# rev3.net
KiCad netlist of a schematic drawn in EAGLE
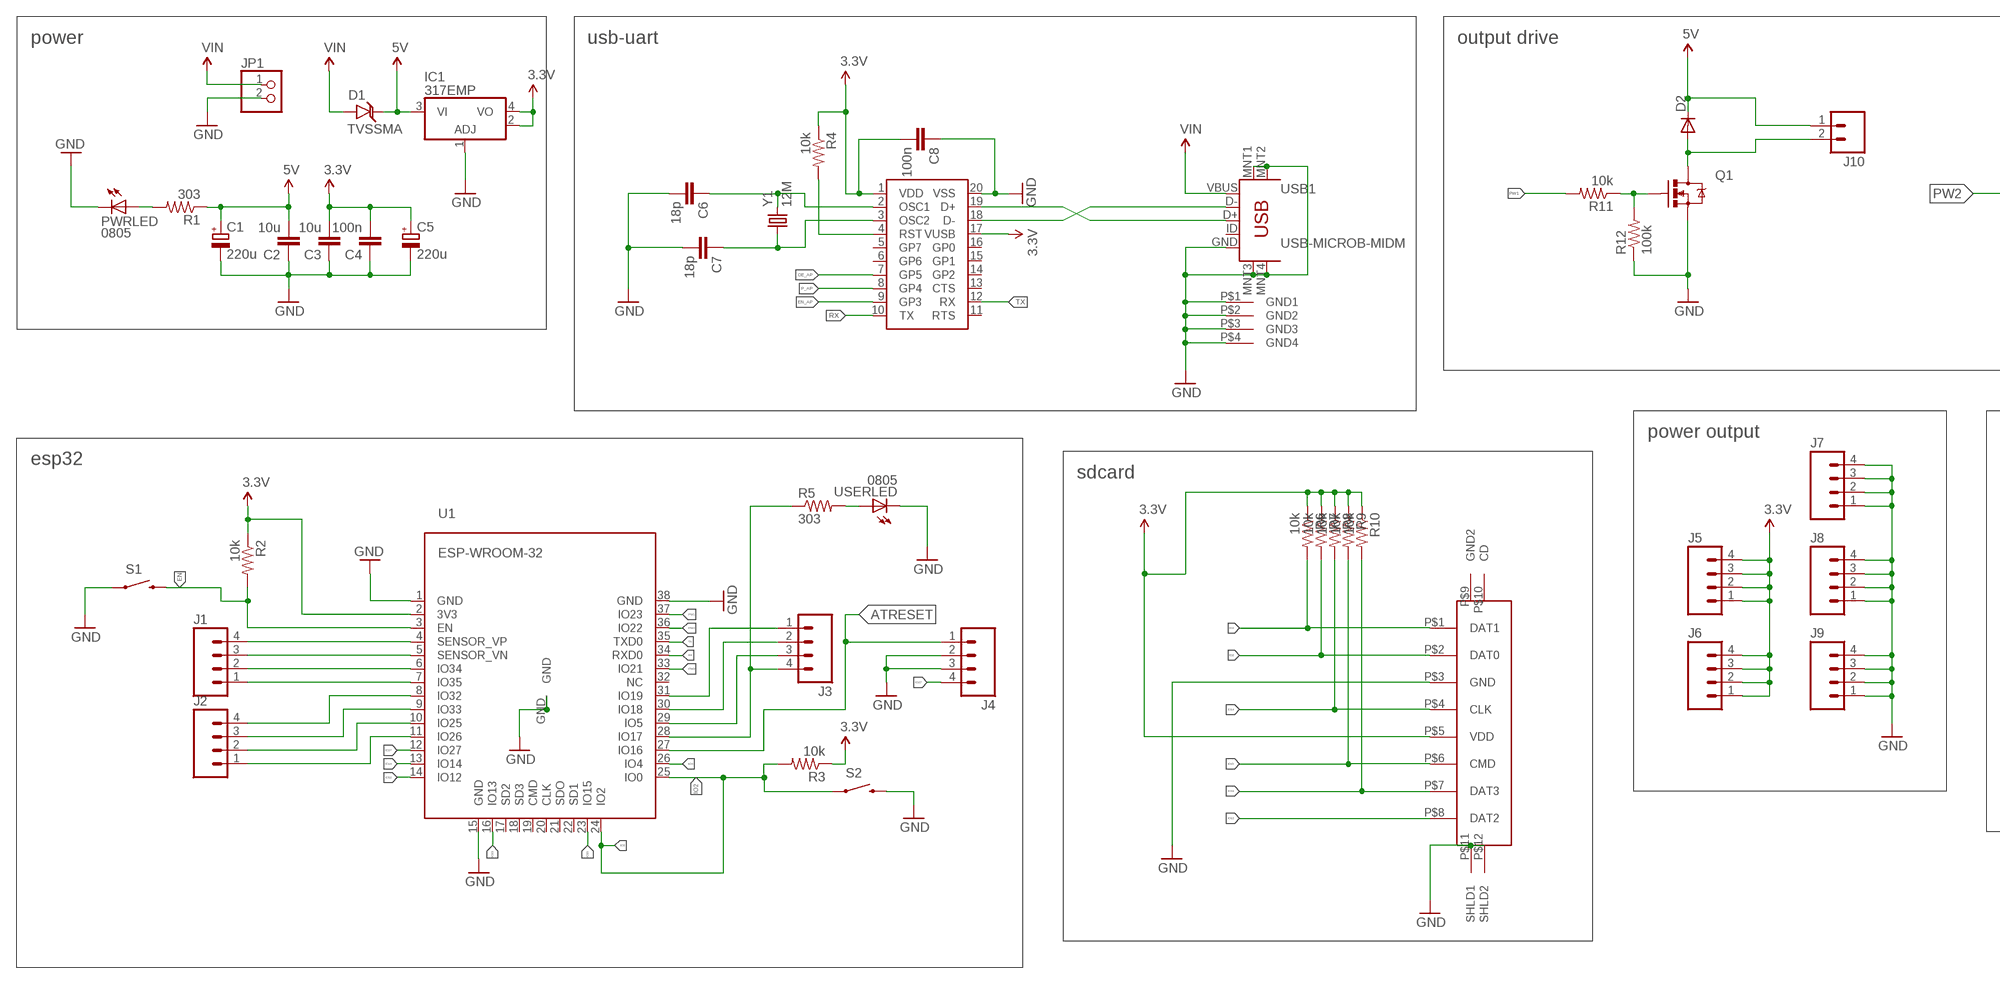
[diagram p0: schematic, sheet 1, part 1 of 2]
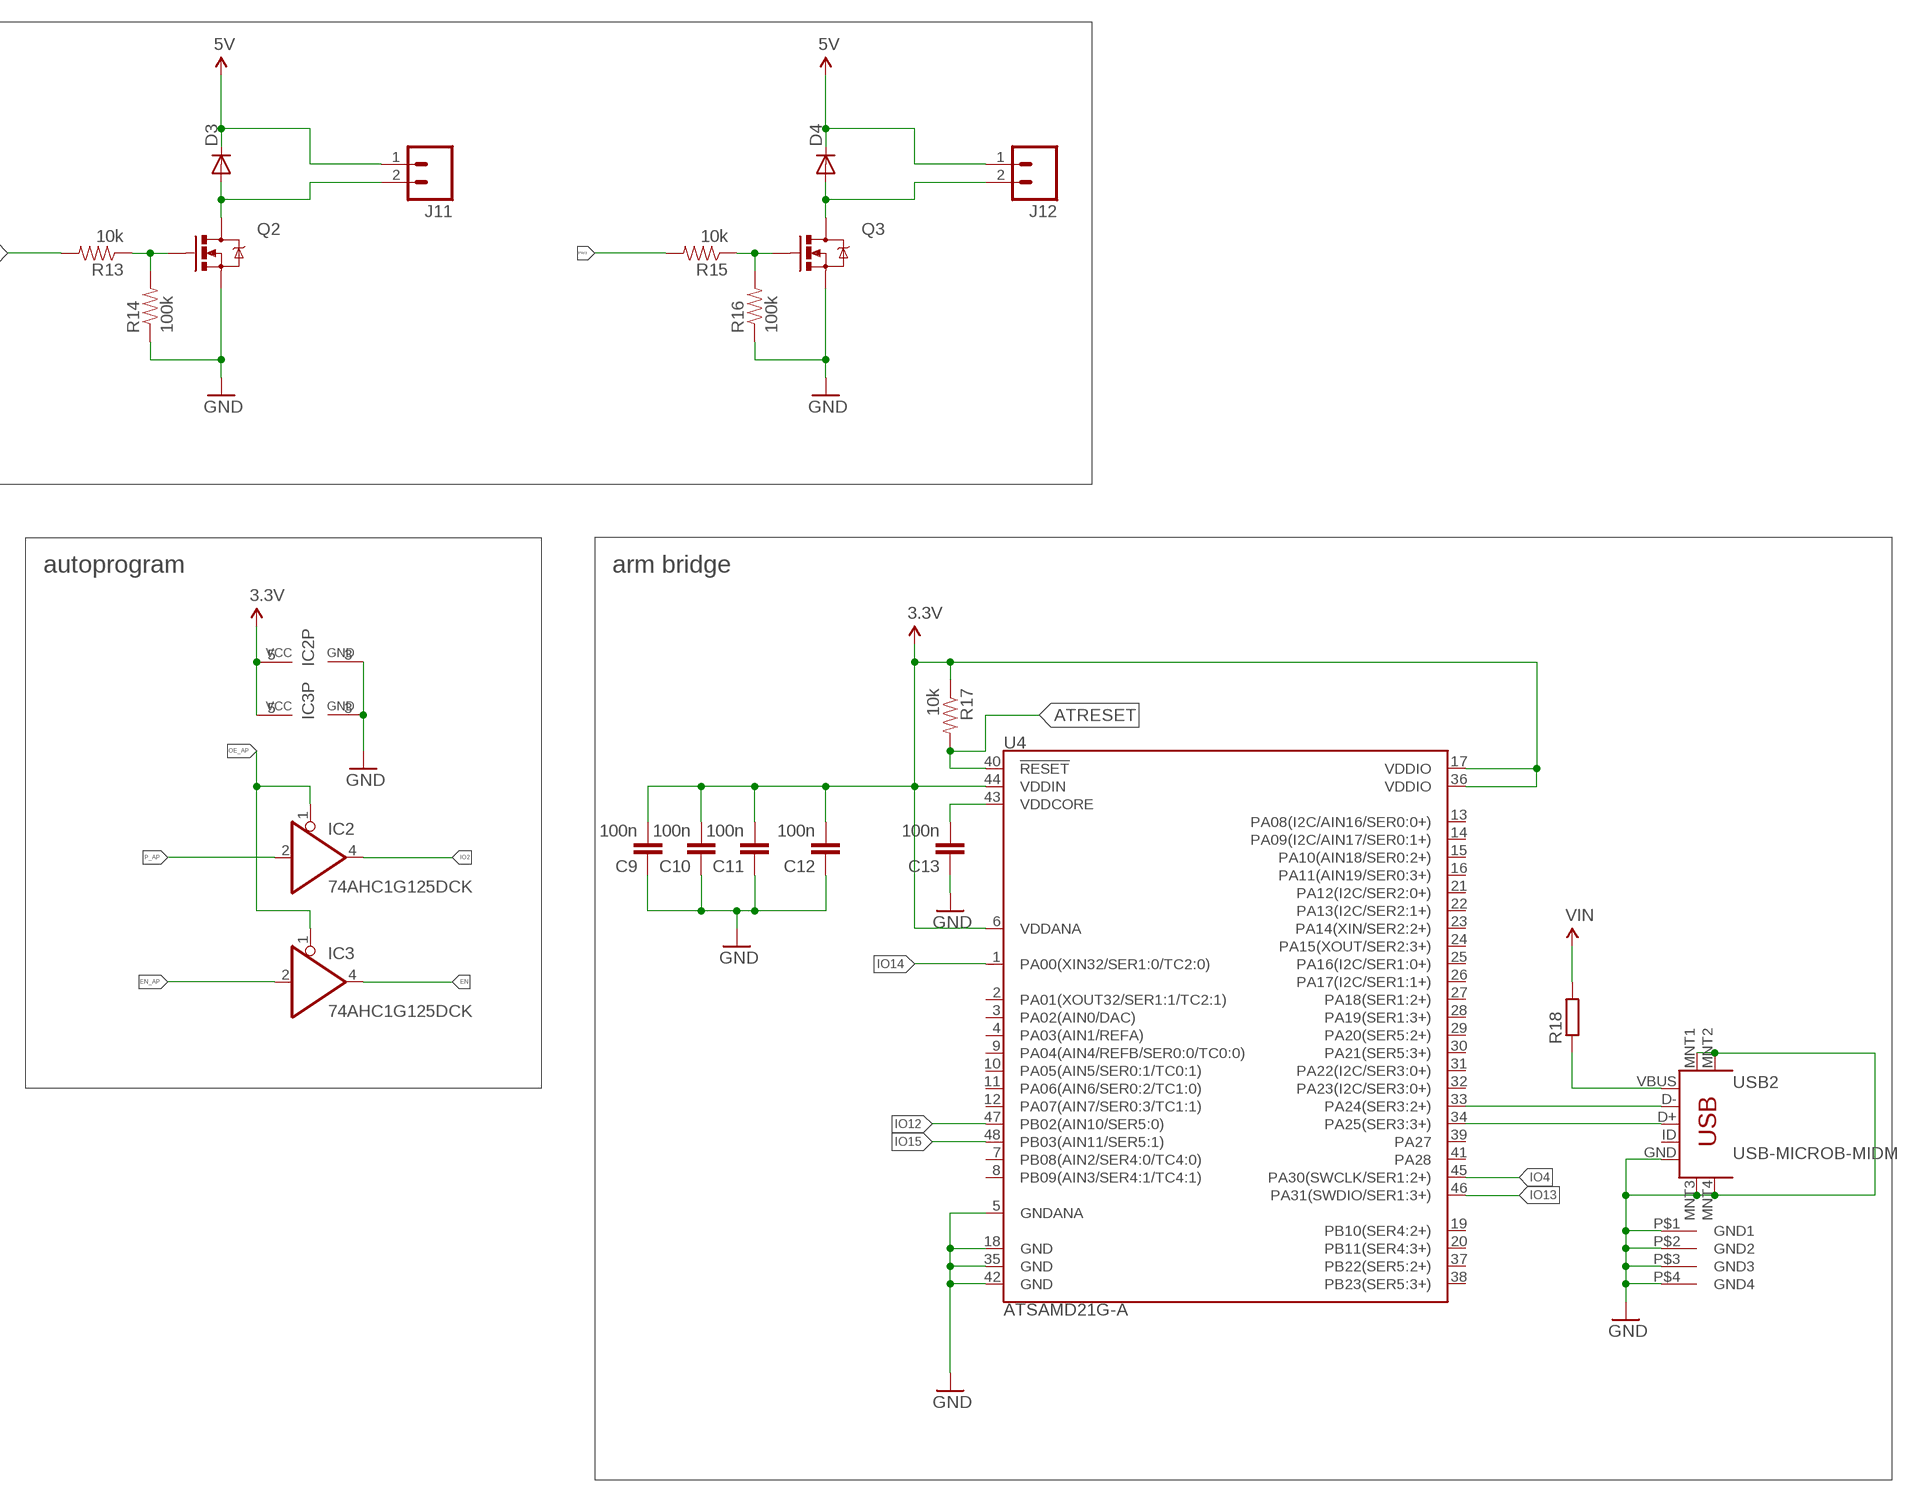
[diagram p1: schematic, sheet 1, part 2 of 2]

(export (version "E")
  (design (tool "Eeschema 10.0.6"))
  (components
    (comp (ref "C1")
      (value "220u")
      (footprint "eagle-import:E2-4")
      (libsource (lib "eagle-import") (part "CPOL-EUE2-4"))
    )
    (comp (ref "C2")
      (value "10u")
      (footprint "eagle-import:0805")
      (libsource (lib "eagle-import") (part "CAP0805"))
    )
    (comp (ref "C3")
      (value "10u")
      (footprint "eagle-import:0805")
      (libsource (lib "eagle-import") (part "CAP0805"))
    )
    (comp (ref "C4")
      (value "100n")
      (footprint "eagle-import:0603-CAP")
      (libsource (lib "eagle-import") (part "CAP0603-CAP"))
    )
    (comp (ref "C5")
      (value "220u")
      (footprint "eagle-import:E2-4")
      (libsource (lib "eagle-import") (part "CPOL-EUE2-4"))
    )
    (comp (ref "C6")
      (value "18p")
      (footprint "eagle-import:0603-CAP")
      (libsource (lib "eagle-import") (part "CAP0603-CAP"))
    )
    (comp (ref "C7")
      (value "18p")
      (footprint "eagle-import:0603-CAP")
      (libsource (lib "eagle-import") (part "CAP0603-CAP"))
    )
    (comp (ref "C8")
      (value "100n")
      (footprint "eagle-import:0603-CAP")
      (libsource (lib "eagle-import") (part "CAP0603-CAP"))
    )
    (comp (ref "C9")
      (value "100n")
      (footprint "eagle-import:C0603K")
      (libsource (lib "eagle-import") (part "C-EUC0603K"))
    )
    (comp (ref "C10")
      (value "100n")
      (footprint "eagle-import:C0603K")
      (libsource (lib "eagle-import") (part "C-EUC0603K"))
    )
    (comp (ref "C11")
      (value "100n")
      (footprint "eagle-import:C0603K")
      (libsource (lib "eagle-import") (part "C-EUC0603K"))
    )
    (comp (ref "C12")
      (value "100n")
      (footprint "eagle-import:C0603K")
      (libsource (lib "eagle-import") (part "C-EUC0603K"))
    )
    (comp (ref "C13")
      (value "100n")
      (footprint "eagle-import:C0603K")
      (libsource (lib "eagle-import") (part "C-EUC0603K"))
    )
    (comp (ref "D1")
      (value "TVSSMA")
      (footprint "eagle-import:SMA-DIODE")
      (libsource (lib "eagle-import") (part "TVSSMA"))
    )
    (comp (ref "D2")
      (value "DIODE-SOD323-W")
      (footprint "eagle-import:SOD323-W")
      (libsource (lib "eagle-import") (part "DIODE-SOD323-W"))
    )
    (comp (ref "D3")
      (value "DIODE-SOD323-W")
      (footprint "eagle-import:SOD323-W")
      (libsource (lib "eagle-import") (part "DIODE-SOD323-W"))
    )
    (comp (ref "D4")
      (value "DIODE-SOD323-W")
      (footprint "eagle-import:SOD323-W")
      (libsource (lib "eagle-import") (part "DIODE-SOD323-W"))
    )
    (comp (ref "IC1")
      (value "317EMP")
      (footprint "eagle-import:SOT223")
      (libsource (lib "eagle-import") (part "317EMP"))
    )
    (comp (ref "IC2")
      (value "74AHC1G125DCK")
      (footprint "eagle-import:SC70-5")
      (libsource (lib "eagle-import") (part "741G125DCKAHC"))
    )
    (comp (ref "IC3")
      (value "74AHC1G125DCK")
      (footprint "eagle-import:SC70-5")
      (libsource (lib "eagle-import") (part "741G125DCKAHC"))
    )
    (comp (ref "J1")
      (value "M04LONGPADS")
      (footprint "eagle-import:1X04_LONGPADS")
      (libsource (lib "eagle-import") (part "M04LONGPADS"))
    )
    (comp (ref "J2")
      (value "M04LONGPADS")
      (footprint "eagle-import:1X04_LONGPADS")
      (libsource (lib "eagle-import") (part "M04LONGPADS"))
    )
    (comp (ref "J3")
      (value "M041.27MM")
      (footprint "eagle-import:1X04-1.27MM")
      (libsource (lib "eagle-import") (part "M041.27MM"))
    )
    (comp (ref "J4")
      (value "M041.27MM")
      (footprint "eagle-import:1X04-1.27MM")
      (libsource (lib "eagle-import") (part "M041.27MM"))
    )
    (comp (ref "J5")
      (value "M04LONGPADS")
      (footprint "eagle-import:1X04_LONGPADS")
      (libsource (lib "eagle-import") (part "M04LONGPADS"))
    )
    (comp (ref "J6")
      (value "M04LONGPADS")
      (footprint "eagle-import:1X04_LONGPADS")
      (libsource (lib "eagle-import") (part "M04LONGPADS"))
    )
    (comp (ref "J7")
      (value "M04LONGPADS")
      (footprint "eagle-import:1X04_LONGPADS")
      (libsource (lib "eagle-import") (part "M04LONGPADS"))
    )
    (comp (ref "J8")
      (value "M04LONGPADS")
      (footprint "eagle-import:1X04_LONGPADS")
      (libsource (lib "eagle-import") (part "M04LONGPADS"))
    )
    (comp (ref "J9")
      (value "M04LONGPADS")
      (footprint "eagle-import:1X04_LONGPADS")
      (libsource (lib "eagle-import") (part "M04LONGPADS"))
    )
    (comp (ref "J10")
      (value "M02LOCK_LONGPADS")
      (footprint "eagle-import:1X02_LOCK_LONGPADS")
      (libsource (lib "eagle-import") (part "M02LOCK_LONGPADS"))
    )
    (comp (ref "J11")
      (value "M02LOCK_LONGPADS")
      (footprint "eagle-import:1X02_LOCK_LONGPADS")
      (libsource (lib "eagle-import") (part "M02LOCK_LONGPADS"))
    )
    (comp (ref "J12")
      (value "M02LOCK_LONGPADS")
      (footprint "eagle-import:1X02_LOCK_LONGPADS")
      (libsource (lib "eagle-import") (part "M02LOCK_LONGPADS"))
    )
    (comp (ref "JP1")
      (value "PINHD-1X2")
      (footprint "eagle-import:1X02")
      (libsource (lib "eagle-import") (part "PINHD-1X2"))
    )
    (comp (ref "PWRLED")
      (value "0805")
      (footprint "eagle-import:SML0805")
      (libsource (lib "eagle-import") (part "LEDSML0805"))
    )
    (comp (ref "Q1")
      (value "MOSFET-NCHANNELBSS138")
      (footprint "eagle-import:SOT23-3")
      (libsource (lib "eagle-import") (part "MOSFET-NCHANNELBSS138"))
    )
    (comp (ref "Q2")
      (value "MOSFET-NCHANNELBSS138")
      (footprint "eagle-import:SOT23-3")
      (libsource (lib "eagle-import") (part "MOSFET-NCHANNELBSS138"))
    )
    (comp (ref "Q3")
      (value "MOSFET-NCHANNELBSS138")
      (footprint "eagle-import:SOT23-3")
      (libsource (lib "eagle-import") (part "MOSFET-NCHANNELBSS138"))
    )
    (comp (ref "R1")
      (value "303")
      (footprint "eagle-import:0805")
      (libsource (lib "eagle-import") (part "RESISTOR0805-RES"))
    )
    (comp (ref "R2")
      (value "10k")
      (footprint "eagle-import:0805")
      (libsource (lib "eagle-import") (part "RESISTOR0805-RES"))
    )
    (comp (ref "R3")
      (value "10k")
      (footprint "eagle-import:0805")
      (libsource (lib "eagle-import") (part "RESISTOR0805-RES"))
    )
    (comp (ref "R4")
      (value "10k")
      (footprint "eagle-import:0805")
      (libsource (lib "eagle-import") (part "RESISTOR0805-RES"))
    )
    (comp (ref "R5")
      (value "303")
      (footprint "eagle-import:0805")
      (libsource (lib "eagle-import") (part "RESISTOR0805-RES"))
    )
    (comp (ref "R6")
      (value "10k")
      (footprint "eagle-import:0805")
      (libsource (lib "eagle-import") (part "RESISTOR0805-RES"))
    )
    (comp (ref "R7")
      (value "10k")
      (footprint "eagle-import:0805")
      (libsource (lib "eagle-import") (part "RESISTOR0805-RES"))
    )
    (comp (ref "R8")
      (value "10k")
      (footprint "eagle-import:0805")
      (libsource (lib "eagle-import") (part "RESISTOR0805-RES"))
    )
    (comp (ref "R9")
      (value "10k")
      (footprint "eagle-import:0805")
      (libsource (lib "eagle-import") (part "RESISTOR0805-RES"))
    )
    (comp (ref "R10")
      (value "10k")
      (footprint "eagle-import:0805")
      (libsource (lib "eagle-import") (part "RESISTOR0805-RES"))
    )
    (comp (ref "R11")
      (value "10k")
      (footprint "eagle-import:0805")
      (libsource (lib "eagle-import") (part "RESISTOR0805-RES"))
    )
    (comp (ref "R12")
      (value "100k")
      (footprint "eagle-import:0805")
      (libsource (lib "eagle-import") (part "RESISTOR0805-RES"))
    )
    (comp (ref "R13")
      (value "10k")
      (footprint "eagle-import:0805")
      (libsource (lib "eagle-import") (part "RESISTOR0805-RES"))
    )
    (comp (ref "R14")
      (value "100k")
      (footprint "eagle-import:0805")
      (libsource (lib "eagle-import") (part "RESISTOR0805-RES"))
    )
    (comp (ref "R15")
      (value "10k")
      (footprint "eagle-import:0805")
      (libsource (lib "eagle-import") (part "RESISTOR0805-RES"))
    )
    (comp (ref "R16")
      (value "100k")
      (footprint "eagle-import:0805")
      (libsource (lib "eagle-import") (part "RESISTOR0805-RES"))
    )
    (comp (ref "R17")
      (value "10k")
      (footprint "eagle-import:0805")
      (libsource (lib "eagle-import") (part "RESISTOR0805-RES"))
    )
    (comp (ref "R18")
      (value "R-EU_R2010W")
      (footprint "eagle-import:R2010W")
      (libsource (lib "eagle-import") (part "R-EU_R2010W"))
    )
    (comp (ref "S1")
      (value "SWITCH-MOMENTARY-2SMD")
      (footprint "eagle-import:TACTILE-SWITCH-SMD")
      (libsource (lib "eagle-import") (part "SWITCH-MOMENTARY-2SMD"))
    )
    (comp (ref "S2")
      (value "SWITCH-MOMENTARY-2SMD")
      (footprint "eagle-import:TACTILE-SWITCH-SMD")
      (libsource (lib "eagle-import") (part "SWITCH-MOMENTARY-2SMD"))
    )
    (comp (ref "U1")
      (value "ESP-WROOM-32")
      (footprint "eagle-import:ESP-WROOM-32")
      (libsource (lib "eagle-import") (part "ESP-WROOM-32"))
    )
    (comp (ref "U2")
      (value "MCP2200")
      (footprint "eagle-import:SO20W")
      (libsource (lib "eagle-import") (part "MCP2200"))
    )
    (comp (ref "U3")
      (value "MICROSD")
      (footprint "eagle-import:MICROSD")
      (libsource (lib "eagle-import") (part "MICROSD"))
    )
    (comp (ref "U4")
      (value "ATSAMD21G-A")
      (footprint "eagle-import:TQFP-48")
      (libsource (lib "eagle-import") (part "ATSAMD21G-A"))
    )
    (comp (ref "USB1")
      (value "USB-MICROB-MIDM")
      (footprint "eagle-import:USB-B-MICRO-MIDM")
      (libsource (lib "eagle-import") (part "USB-MICROB-MIDM"))
    )
    (comp (ref "USB2")
      (value "USB-MICROB-MIDM")
      (footprint "eagle-import:USB-B-MICRO-MIDM")
      (libsource (lib "eagle-import") (part "USB-MICROB-MIDM"))
    )
    (comp (ref "USERLED")
      (value "0805")
      (footprint "eagle-import:SML0805")
      (libsource (lib "eagle-import") (part "LEDSML0805"))
    )
    (comp (ref "Y1")
      (value "12M")
      (footprint "eagle-import:CRYSTAL-TXC-7A")
      (libsource (lib "eagle-import") (part "CRYSTALTXC-7A"))
    )
  )
  (nets
    (net (code "1") (name "3.3V") (class "Default")
      (node (ref "C10") (pin "2") (pinfunction "2_2") (pintype "passive"))
      (node (ref "C11") (pin "2") (pinfunction "2_2") (pintype "passive"))
      (node (ref "C12") (pin "2") (pinfunction "2_2") (pintype "passive"))
      (node (ref "C3") (pin "2") (pinfunction "2_2") (pintype "passive"))
      (node (ref "C4") (pin "2") (pinfunction "2_2") (pintype "passive"))
      (node (ref "C5") (pin "+") (pinfunction "+_+") (pintype "passive"))
      (node (ref "C8") (pin "2") (pinfunction "2_2") (pintype "passive"))
      (node (ref "C9") (pin "2") (pinfunction "2_2") (pintype "passive"))
      (node (ref "IC1") (pin "2") (pinfunction "VO2_2") (pintype "passive"))
      (node (ref "IC1") (pin "4") (pinfunction "VO_4") (pintype "passive"))
      (node (ref "IC2") (pin "5") (pinfunction "VCC_5") (pintype "power_in"))
      (node (ref "IC3") (pin "5") (pinfunction "VCC_5") (pintype "power_in"))
      (node (ref "J5") (pin "1") (pinfunction "1_1") (pintype "passive"))
      (node (ref "J5") (pin "2") (pinfunction "2_2") (pintype "passive"))
      (node (ref "J5") (pin "3") (pinfunction "3_3") (pintype "passive"))
      (node (ref "J5") (pin "4") (pinfunction "4_4") (pintype "passive"))
      (node (ref "J6") (pin "1") (pinfunction "1_1") (pintype "passive"))
      (node (ref "J6") (pin "2") (pinfunction "2_2") (pintype "passive"))
      (node (ref "J6") (pin "3") (pinfunction "3_3") (pintype "passive"))
      (node (ref "J6") (pin "4") (pinfunction "4_4") (pintype "passive"))
      (node (ref "R10") (pin "1") (pinfunction "1_1") (pintype "passive"))
      (node (ref "R17") (pin "1") (pinfunction "1_1") (pintype "passive"))
      (node (ref "R2") (pin "1") (pinfunction "1_1") (pintype "passive"))
      (node (ref "R3") (pin "1") (pinfunction "1_1") (pintype "passive"))
      (node (ref "R4") (pin "1") (pinfunction "1_1") (pintype "passive"))
      (node (ref "R6") (pin "1") (pinfunction "1_1") (pintype "passive"))
      (node (ref "R7") (pin "1") (pinfunction "1_1") (pintype "passive"))
      (node (ref "R8") (pin "1") (pinfunction "1_1") (pintype "passive"))
      (node (ref "R9") (pin "1") (pinfunction "1_1") (pintype "passive"))
      (node (ref "U1") (pin "2") (pinfunction "3V3_2") (pintype "bidirectional"))
      (node (ref "U2") (pin "1") (pinfunction "VDD_1") (pintype "bidirectional"))
      (node (ref "U2") (pin "17") (pinfunction "VUSB_17") (pintype "bidirectional"))
      (node (ref "U3") (pin "P$5") (pinfunction "VDD_P$5") (pintype "bidirectional"))
      (node (ref "U4") (pin "17") (pinfunction "VDDIO_17") (pintype "bidirectional"))
      (node (ref "U4") (pin "36") (pinfunction "VDDIO_36") (pintype "bidirectional"))
      (node (ref "U4") (pin "44") (pinfunction "VDDIN_44") (pintype "bidirectional"))
      (node (ref "U4") (pin "6") (pinfunction "VDDANA_6") (pintype "bidirectional"))
    )
    (net (code "2") (name "5V") (class "Default")
      (node (ref "C1") (pin "+") (pinfunction "+_+") (pintype "passive"))
      (node (ref "C2") (pin "2") (pinfunction "2_2") (pintype "passive"))
      (node (ref "D1") (pin "C") (pinfunction "C_C") (pintype "passive"))
      (node (ref "D2") (pin "C") (pinfunction "C_C") (pintype "passive"))
      (node (ref "D3") (pin "C") (pinfunction "C_C") (pintype "passive"))
      (node (ref "D4") (pin "C") (pinfunction "C_C") (pintype "passive"))
      (node (ref "IC1") (pin "3") (pinfunction "VI_3") (pintype "input"))
      (node (ref "J10") (pin "1") (pinfunction "1_1") (pintype "passive"))
      (node (ref "J11") (pin "1") (pinfunction "1_1") (pintype "passive"))
      (node (ref "J12") (pin "1") (pinfunction "1_1") (pintype "passive"))
      (node (ref "R1") (pin "1") (pinfunction "1_1") (pintype "passive"))
    )
    (net (code "3") (name "ATRESET") (class "Default")
      (node (ref "J4") (pin "1") (pinfunction "1_1") (pintype "passive"))
      (node (ref "R17") (pin "2") (pinfunction "2_2") (pintype "passive"))
      (node (ref "U1") (pin "27") (pinfunction "IO16_27") (pintype "bidirectional"))
      (node (ref "U4") (pin "40") (pinfunction "~{RESET}_40") (pintype "bidirectional"))
    )
    (net (code "4") (name "EN") (class "Default")
      (node (ref "IC3") (pin "4") (pinfunction "O_4") (pintype "tri_state"))
      (node (ref "R2") (pin "2") (pinfunction "2_2") (pintype "passive"))
      (node (ref "S1") (pin "3") (pinfunction "2_3") (pintype "passive"))
      (node (ref "U1") (pin "3") (pinfunction "EN_3") (pintype "bidirectional"))
    )
    (net (code "5") (name "EN_AP") (class "Default")
      (node (ref "IC3") (pin "2") (pinfunction "I_2") (pintype "input"))
      (node (ref "U2") (pin "9") (pinfunction "GP3_9") (pintype "bidirectional"))
    )
    (net (code "6") (name "GND") (class "Default")
      (node (ref "C1") (pin "-") (pinfunction "-_-") (pintype "passive"))
      (node (ref "C10") (pin "1") (pinfunction "1_1") (pintype "passive"))
      (node (ref "C11") (pin "1") (pinfunction "1_1") (pintype "passive"))
      (node (ref "C12") (pin "1") (pinfunction "1_1") (pintype "passive"))
      (node (ref "C13") (pin "1") (pinfunction "1_1") (pintype "passive"))
      (node (ref "C2") (pin "1") (pinfunction "1_1") (pintype "passive"))
      (node (ref "C3") (pin "1") (pinfunction "1_1") (pintype "passive"))
      (node (ref "C4") (pin "1") (pinfunction "1_1") (pintype "passive"))
      (node (ref "C5") (pin "-") (pinfunction "-_-") (pintype "passive"))
      (node (ref "C6") (pin "2") (pinfunction "2_2") (pintype "passive"))
      (node (ref "C7") (pin "2") (pinfunction "2_2") (pintype "passive"))
      (node (ref "C8") (pin "1") (pinfunction "1_1") (pintype "passive"))
      (node (ref "C9") (pin "1") (pinfunction "1_1") (pintype "passive"))
      (node (ref "IC1") (pin "1") (pinfunction "ADJ_1") (pintype "input"))
      (node (ref "IC2") (pin "3") (pinfunction "GND_3") (pintype "power_in"))
      (node (ref "IC3") (pin "3") (pinfunction "GND_3") (pintype "power_in"))
      (node (ref "J4") (pin "2") (pinfunction "2_2") (pintype "passive"))
      (node (ref "J4") (pin "3") (pinfunction "3_3") (pintype "passive"))
      (node (ref "J7") (pin "1") (pinfunction "1_1") (pintype "passive"))
      (node (ref "J7") (pin "2") (pinfunction "2_2") (pintype "passive"))
      (node (ref "J7") (pin "3") (pinfunction "3_3") (pintype "passive"))
      (node (ref "J7") (pin "4") (pinfunction "4_4") (pintype "passive"))
      (node (ref "J8") (pin "1") (pinfunction "1_1") (pintype "passive"))
      (node (ref "J8") (pin "2") (pinfunction "2_2") (pintype "passive"))
      (node (ref "J8") (pin "3") (pinfunction "3_3") (pintype "passive"))
      (node (ref "J8") (pin "4") (pinfunction "4_4") (pintype "passive"))
      (node (ref "J9") (pin "1") (pinfunction "1_1") (pintype "passive"))
      (node (ref "J9") (pin "2") (pinfunction "2_2") (pintype "passive"))
      (node (ref "J9") (pin "3") (pinfunction "3_3") (pintype "passive"))
      (node (ref "J9") (pin "4") (pinfunction "4_4") (pintype "passive"))
      (node (ref "JP1") (pin "2") (pinfunction "2_2") (pintype "passive"))
      (node (ref "PWRLED") (pin "C") (pinfunction "C_C") (pintype "passive"))
      (node (ref "Q1") (pin "2") (pinfunction "S_2") (pintype "passive"))
      (node (ref "Q2") (pin "2") (pinfunction "S_2") (pintype "passive"))
      (node (ref "Q3") (pin "2") (pinfunction "S_2") (pintype "passive"))
      (node (ref "R12") (pin "1") (pinfunction "1_1") (pintype "passive"))
      (node (ref "R14") (pin "1") (pinfunction "1_1") (pintype "passive"))
      (node (ref "R16") (pin "1") (pinfunction "1_1") (pintype "passive"))
      (node (ref "S1") (pin "1") (pinfunction "1_1") (pintype "passive"))
      (node (ref "S2") (pin "3") (pinfunction "2_3") (pintype "passive"))
      (node (ref "U1") (pin "1") (pinfunction "GND_1") (pintype "bidirectional"))
      (node (ref "U1") (pin "15") (pinfunction "GND_15") (pintype "bidirectional"))
      (node (ref "U1") (pin "38") (pinfunction "GND_38") (pintype "bidirectional"))
      (node (ref "U1") (pin "GND") (pinfunction "GND_GND") (pintype "bidirectional"))
      (node (ref "U2") (pin "20") (pinfunction "VSS_20") (pintype "bidirectional"))
      (node (ref "U3") (pin "P$11") (pinfunction "SHLD1_P$11") (pintype "bidirectional"))
      (node (ref "U3") (pin "P$12") (pinfunction "SHLD2_P$12") (pintype "bidirectional"))
      (node (ref "U3") (pin "P$3") (pinfunction "GND_P$3") (pintype "bidirectional"))
      (node (ref "U4") (pin "18") (pinfunction "GND_18") (pintype "bidirectional"))
      (node (ref "U4") (pin "35") (pinfunction "GND_35") (pintype "bidirectional"))
      (node (ref "U4") (pin "42") (pinfunction "GND_42") (pintype "bidirectional"))
      (node (ref "U4") (pin "5") (pinfunction "GNDANA_5") (pintype "bidirectional"))
      (node (ref "USB1") (pin "GND") (pinfunction "GND_GND") (pintype "bidirectional"))
      (node (ref "USB1") (pin "MNT1") (pinfunction "MTN1_MNT1") (pintype "bidirectional"))
      (node (ref "USB1") (pin "MNT2") (pinfunction "MTN2_MNT2") (pintype "bidirectional"))
      (node (ref "USB1") (pin "MNT3") (pinfunction "MTN3_MNT3") (pintype "bidirectional"))
      (node (ref "USB1") (pin "MNT4") (pinfunction "MTN4_MNT4") (pintype "bidirectional"))
      (node (ref "USB1") (pin "P$1") (pinfunction "GND1_P$1") (pintype "bidirectional"))
      (node (ref "USB1") (pin "P$2") (pinfunction "GND2_P$2") (pintype "bidirectional"))
      (node (ref "USB1") (pin "P$3") (pinfunction "GND3_P$3") (pintype "bidirectional"))
      (node (ref "USB1") (pin "P$4") (pinfunction "GND4_P$4") (pintype "bidirectional"))
      (node (ref "USB2") (pin "GND") (pinfunction "GND_GND") (pintype "bidirectional"))
      (node (ref "USB2") (pin "MNT1") (pinfunction "MTN1_MNT1") (pintype "bidirectional"))
      (node (ref "USB2") (pin "MNT2") (pinfunction "MTN2_MNT2") (pintype "bidirectional"))
      (node (ref "USB2") (pin "MNT3") (pinfunction "MTN3_MNT3") (pintype "bidirectional"))
      (node (ref "USB2") (pin "MNT4") (pinfunction "MTN4_MNT4") (pintype "bidirectional"))
      (node (ref "USB2") (pin "P$1") (pinfunction "GND1_P$1") (pintype "bidirectional"))
      (node (ref "USB2") (pin "P$2") (pinfunction "GND2_P$2") (pintype "bidirectional"))
      (node (ref "USB2") (pin "P$3") (pinfunction "GND3_P$3") (pintype "bidirectional"))
      (node (ref "USB2") (pin "P$4") (pinfunction "GND4_P$4") (pintype "bidirectional"))
      (node (ref "USERLED") (pin "C") (pinfunction "C_C") (pintype "passive"))
    )
    (net (code "7") (name "IO2") (class "Default")
      (node (ref "IC2") (pin "4") (pinfunction "O_4") (pintype "tri_state"))
      (node (ref "R3") (pin "2") (pinfunction "2_2") (pintype "passive"))
      (node (ref "R7") (pin "2") (pinfunction "2_2") (pintype "passive"))
      (node (ref "S2") (pin "1") (pinfunction "1_1") (pintype "passive"))
      (node (ref "U1") (pin "24") (pinfunction "IO2_24") (pintype "bidirectional"))
      (node (ref "U1") (pin "25") (pinfunction "IO0_25") (pintype "bidirectional"))
      (node (ref "U3") (pin "P$2") (pinfunction "DAT0_P$2") (pintype "bidirectional"))
    )
    (net (code "8") (name "IO4") (class "Default")
      (node (ref "R6") (pin "2") (pinfunction "2_2") (pintype "passive"))
      (node (ref "U1") (pin "26") (pinfunction "IO4_26") (pintype "bidirectional"))
      (node (ref "U3") (pin "P$1") (pinfunction "DAT1_P$1") (pintype "bidirectional"))
      (node (ref "U4") (pin "45") (pinfunction "PA30(SWCLK/SER1:2+)_45") (pintype "bidirectional"))
    )
    (net (code "9") (name "IO12") (class "Default")
      (node (ref "U1") (pin "14") (pinfunction "IO12_14") (pintype "bidirectional"))
      (node (ref "U3") (pin "P$8") (pinfunction "DAT2_P$8") (pintype "bidirectional"))
      (node (ref "U4") (pin "47") (pinfunction "PB02(AIN10/SER5:0)_47") (pintype "bidirectional"))
    )
    (net (code "10") (name "IO13") (class "Default")
      (node (ref "R10") (pin "2") (pinfunction "2_2") (pintype "passive"))
      (node (ref "U1") (pin "16") (pinfunction "IO13_16") (pintype "bidirectional"))
      (node (ref "U3") (pin "P$7") (pinfunction "DAT3_P$7") (pintype "bidirectional"))
      (node (ref "U4") (pin "46") (pinfunction "PA31(SWDIO/SER1:3+)_46") (pintype "bidirectional"))
    )
    (net (code "11") (name "IO14") (class "Default")
      (node (ref "R8") (pin "2") (pinfunction "2_2") (pintype "passive"))
      (node (ref "U1") (pin "13") (pinfunction "IO14_13") (pintype "bidirectional"))
      (node (ref "U3") (pin "P$4") (pinfunction "CLK_P$4") (pintype "bidirectional"))
      (node (ref "U4") (pin "1") (pinfunction "PA00(XIN32/SER1:0/TC2:0)_1") (pintype "bidirectional"))
    )
    (net (code "12") (name "IO15") (class "Default")
      (node (ref "R9") (pin "2") (pinfunction "2_2") (pintype "passive"))
      (node (ref "U1") (pin "23") (pinfunction "IO15_23") (pintype "bidirectional"))
      (node (ref "U3") (pin "P$6") (pinfunction "CMD_P$6") (pintype "bidirectional"))
      (node (ref "U4") (pin "48") (pinfunction "PB03(AIN11/SER5:1)_48") (pintype "bidirectional"))
    )
    (net (code "13") (name "IO27") (class "Default")
      (node (ref "J4") (pin "4") (pinfunction "4_4") (pintype "passive"))
      (node (ref "U1") (pin "12") (pinfunction "IO27_12") (pintype "bidirectional"))
    )
    (net (code "14") (name "Net-(PWRLED-PadA)") (class "Default")
      (node (ref "PWRLED") (pin "A") (pinfunction "A_A") (pintype "passive"))
      (node (ref "R1") (pin "2") (pinfunction "2_2") (pintype "passive"))
    )
    (net (code "15") (name "Net-(Q1-D)") (class "Default")
      (node (ref "D2") (pin "A") (pinfunction "A_A") (pintype "passive"))
      (node (ref "J10") (pin "2") (pinfunction "2_2") (pintype "passive"))
      (node (ref "Q1") (pin "3") (pinfunction "D_3") (pintype "passive"))
    )
    (net (code "16") (name "Net-(Q1-G)") (class "Default")
      (node (ref "Q1") (pin "1") (pinfunction "G_1") (pintype "passive"))
      (node (ref "R11") (pin "1") (pinfunction "1_1") (pintype "passive"))
      (node (ref "R12") (pin "2") (pinfunction "2_2") (pintype "passive"))
    )
    (net (code "17") (name "Net-(Q2-D)") (class "Default")
      (node (ref "D3") (pin "A") (pinfunction "A_A") (pintype "passive"))
      (node (ref "J11") (pin "2") (pinfunction "2_2") (pintype "passive"))
      (node (ref "Q2") (pin "3") (pinfunction "D_3") (pintype "passive"))
    )
    (net (code "18") (name "Net-(Q2-G)") (class "Default")
      (node (ref "Q2") (pin "1") (pinfunction "G_1") (pintype "passive"))
      (node (ref "R13") (pin "1") (pinfunction "1_1") (pintype "passive"))
      (node (ref "R14") (pin "2") (pinfunction "2_2") (pintype "passive"))
    )
    (net (code "19") (name "Net-(Q3-D)") (class "Default")
      (node (ref "D4") (pin "A") (pinfunction "A_A") (pintype "passive"))
      (node (ref "J12") (pin "2") (pinfunction "2_2") (pintype "passive"))
      (node (ref "Q3") (pin "3") (pinfunction "D_3") (pintype "passive"))
    )
    (net (code "20") (name "Net-(Q3-G)") (class "Default")
      (node (ref "Q3") (pin "1") (pinfunction "G_1") (pintype "passive"))
      (node (ref "R15") (pin "1") (pinfunction "1_1") (pintype "passive"))
      (node (ref "R16") (pin "2") (pinfunction "2_2") (pintype "passive"))
    )
    (net (code "21") (name "Net-(R5-Pad2)") (class "Default")
      (node (ref "R5") (pin "2") (pinfunction "2_2") (pintype "passive"))
      (node (ref "USERLED") (pin "A") (pinfunction "A_A") (pintype "passive"))
    )
    (net (code "22") (name "Net-(R18-Pad1)") (class "Default")
      (node (ref "R18") (pin "1") (pinfunction "1_1") (pintype "passive"))
      (node (ref "USB2") (pin "VBUS") (pinfunction "VBUS_VBUS") (pintype "bidirectional"))
    )
    (net (code "23") (name "Net-(U1-IO5)") (class "Default")
      (node (ref "J3") (pin "3") (pinfunction "3_3") (pintype "passive"))
      (node (ref "U1") (pin "29") (pinfunction "IO5_29") (pintype "bidirectional"))
    )
    (net (code "24") (name "Net-(U1-IO17)") (class "Default")
      (node (ref "J3") (pin "4") (pinfunction "4_4") (pintype "passive"))
      (node (ref "R5") (pin "1") (pinfunction "1_1") (pintype "passive"))
      (node (ref "U1") (pin "28") (pinfunction "IO17_28") (pintype "bidirectional"))
    )
    (net (code "25") (name "Net-(U1-IO18)") (class "Default")
      (node (ref "J3") (pin "2") (pinfunction "2_2") (pintype "passive"))
      (node (ref "U1") (pin "30") (pinfunction "IO18_30") (pintype "bidirectional"))
    )
    (net (code "26") (name "Net-(U1-IO19)") (class "Default")
      (node (ref "J3") (pin "1") (pinfunction "1_1") (pintype "passive"))
      (node (ref "U1") (pin "31") (pinfunction "IO19_31") (pintype "bidirectional"))
    )
    (net (code "27") (name "Net-(U1-IO25)") (class "Default")
      (node (ref "J2") (pin "2") (pinfunction "2_2") (pintype "passive"))
      (node (ref "U1") (pin "10") (pinfunction "IO25_10") (pintype "bidirectional"))
    )
    (net (code "28") (name "Net-(U1-IO26)") (class "Default")
      (node (ref "J2") (pin "1") (pinfunction "1_1") (pintype "passive"))
      (node (ref "U1") (pin "11") (pinfunction "IO26_11") (pintype "bidirectional"))
    )
    (net (code "29") (name "Net-(U1-IO32)") (class "Default")
      (node (ref "J2") (pin "4") (pinfunction "4_4") (pintype "passive"))
      (node (ref "U1") (pin "8") (pinfunction "IO32_8") (pintype "bidirectional"))
    )
    (net (code "30") (name "Net-(U1-IO33)") (class "Default")
      (node (ref "J2") (pin "3") (pinfunction "3_3") (pintype "passive"))
      (node (ref "U1") (pin "9") (pinfunction "IO33_9") (pintype "bidirectional"))
    )
    (net (code "31") (name "Net-(U1-IO34)") (class "Default")
      (node (ref "J1") (pin "2") (pinfunction "2_2") (pintype "passive"))
      (node (ref "U1") (pin "6") (pinfunction "IO34_6") (pintype "bidirectional"))
    )
    (net (code "32") (name "Net-(U1-IO35)") (class "Default")
      (node (ref "J1") (pin "1") (pinfunction "1_1") (pintype "passive"))
      (node (ref "U1") (pin "7") (pinfunction "IO35_7") (pintype "bidirectional"))
    )
    (net (code "33") (name "Net-(U1-SENSOR_VN)") (class "Default")
      (node (ref "J1") (pin "3") (pinfunction "3_3") (pintype "passive"))
      (node (ref "U1") (pin "5") (pinfunction "SENSOR_VN_5") (pintype "bidirectional"))
    )
    (net (code "34") (name "Net-(U1-SENSOR_VP)") (class "Default")
      (node (ref "J1") (pin "4") (pinfunction "4_4") (pintype "passive"))
      (node (ref "U1") (pin "4") (pinfunction "SENSOR_VP_4") (pintype "bidirectional"))
    )
    (net (code "35") (name "Net-(U2-D+)") (class "Default")
      (node (ref "U2") (pin "19") (pinfunction "D+_19") (pintype "bidirectional"))
      (node (ref "USB1") (pin "D+") (pinfunction "D+_D+") (pintype "bidirectional"))
    )
    (net (code "36") (name "Net-(U2-D-)") (class "Default")
      (node (ref "U2") (pin "18") (pinfunction "D-_18") (pintype "bidirectional"))
      (node (ref "USB1") (pin "D-") (pinfunction "D-_D-") (pintype "bidirectional"))
    )
    (net (code "37") (name "Net-(U2-OSC1)") (class "Default")
      (node (ref "C6") (pin "1") (pinfunction "1_1") (pintype "passive"))
      (node (ref "U2") (pin "2") (pinfunction "OSC1_2") (pintype "bidirectional"))
      (node (ref "Y1") (pin "P$2") (pinfunction "2_P$2") (pintype "passive"))
    )
    (net (code "38") (name "Net-(U2-OSC2)") (class "Default")
      (node (ref "C7") (pin "1") (pinfunction "1_1") (pintype "passive"))
      (node (ref "U2") (pin "3") (pinfunction "OSC2_3") (pintype "bidirectional"))
      (node (ref "Y1") (pin "P$1") (pinfunction "1_P$1") (pintype "passive"))
    )
    (net (code "39") (name "Net-(U2-RST)") (class "Default")
      (node (ref "R4") (pin "2") (pinfunction "2_2") (pintype "passive"))
      (node (ref "U2") (pin "4") (pinfunction "RST_4") (pintype "bidirectional"))
    )
    (net (code "40") (name "Net-(U4-PA24(SER3:2+))") (class "Default")
      (node (ref "U4") (pin "33") (pinfunction "PA24(SER3:2+)_33") (pintype "bidirectional"))
      (node (ref "USB2") (pin "D-") (pinfunction "D-_D-") (pintype "bidirectional"))
    )
    (net (code "41") (name "Net-(U4-PA25(SER3:3+))") (class "Default")
      (node (ref "U4") (pin "34") (pinfunction "PA25(SER3:3+)_34") (pintype "bidirectional"))
      (node (ref "USB2") (pin "D+") (pinfunction "D+_D+") (pintype "bidirectional"))
    )
    (net (code "42") (name "Net-(U4-VDDCORE)") (class "Default")
      (node (ref "C13") (pin "2") (pinfunction "2_2") (pintype "passive"))
      (node (ref "U4") (pin "43") (pinfunction "VDDCORE_43") (pintype "bidirectional"))
    )
    (net (code "43") (name "OE_AP") (class "Default")
      (node (ref "IC2") (pin "1") (pinfunction "OE_1") (pintype "input"))
      (node (ref "IC3") (pin "1") (pinfunction "OE_1") (pintype "input"))
      (node (ref "U2") (pin "7") (pinfunction "GP5_7") (pintype "bidirectional"))
    )
    (net (code "44") (name "PW1") (class "Default")
      (node (ref "R11") (pin "2") (pinfunction "2_2") (pintype "passive"))
      (node (ref "U1") (pin "37") (pinfunction "IO23_37") (pintype "bidirectional"))
    )
    (net (code "45") (name "PW2") (class "Default")
      (node (ref "R13") (pin "2") (pinfunction "2_2") (pintype "passive"))
      (node (ref "U1") (pin "36") (pinfunction "IO22_36") (pintype "bidirectional"))
    )
    (net (code "46") (name "PW3") (class "Default")
      (node (ref "R15") (pin "2") (pinfunction "2_2") (pintype "passive"))
      (node (ref "U1") (pin "33") (pinfunction "IO21_33") (pintype "bidirectional"))
    )
    (net (code "47") (name "P_AP") (class "Default")
      (node (ref "IC2") (pin "2") (pinfunction "I_2") (pintype "input"))
      (node (ref "U2") (pin "8") (pinfunction "GP4_8") (pintype "bidirectional"))
    )
    (net (code "48") (name "RX") (class "Default")
      (node (ref "U1") (pin "34") (pinfunction "RXD0_34") (pintype "bidirectional"))
      (node (ref "U2") (pin "10") (pinfunction "TX_10") (pintype "bidirectional"))
    )
    (net (code "49") (name "TX") (class "Default")
      (node (ref "U1") (pin "35") (pinfunction "TXD0_35") (pintype "bidirectional"))
      (node (ref "U2") (pin "12") (pinfunction "RX_12") (pintype "bidirectional"))
    )
    (net (code "50") (name "VIN") (class "Default")
      (node (ref "D1") (pin "A") (pinfunction "A_A") (pintype "passive"))
      (node (ref "JP1") (pin "1") (pinfunction "1_1") (pintype "passive"))
      (node (ref "R18") (pin "2") (pinfunction "2_2") (pintype "passive"))
      (node (ref "USB1") (pin "VBUS") (pinfunction "VBUS_VBUS") (pintype "bidirectional"))
    )
    (net (code "51") (name "unconnected-(U1-CLK-Pad20)") (class "Default")
      (node (ref "U1") (pin "20") (pinfunction "CLK_20") (pintype "bidirectional"))
    )
    (net (code "52") (name "unconnected-(U1-CMD-Pad19)") (class "Default")
      (node (ref "U1") (pin "19") (pinfunction "CMD_19") (pintype "bidirectional"))
    )
    (net (code "53") (name "unconnected-(U1-NC-Pad32)") (class "Default")
      (node (ref "U1") (pin "32") (pinfunction "NC_32") (pintype "bidirectional"))
    )
    (net (code "54") (name "unconnected-(U1-SD1-Pad22)") (class "Default")
      (node (ref "U1") (pin "22") (pinfunction "SD1_22") (pintype "bidirectional"))
    )
    (net (code "55") (name "unconnected-(U1-SD2-Pad17)") (class "Default")
      (node (ref "U1") (pin "17") (pinfunction "SD2_17") (pintype "bidirectional"))
    )
    (net (code "56") (name "unconnected-(U1-SD3-Pad18)") (class "Default")
      (node (ref "U1") (pin "18") (pinfunction "SD3_18") (pintype "bidirectional"))
    )
    (net (code "57") (name "unconnected-(U1-SDO-Pad21)") (class "Default")
      (node (ref "U1") (pin "21") (pinfunction "SDO_21") (pintype "bidirectional"))
    )
    (net (code "58") (name "unconnected-(U2-CTS-Pad13)") (class "Default")
      (node (ref "U2") (pin "13") (pinfunction "CTS_13") (pintype "bidirectional"))
    )
    (net (code "59") (name "unconnected-(U2-GP0-Pad16)") (class "Default")
      (node (ref "U2") (pin "16") (pinfunction "GP0_16") (pintype "bidirectional"))
    )
    (net (code "60") (name "unconnected-(U2-GP1-Pad15)") (class "Default")
      (node (ref "U2") (pin "15") (pinfunction "GP1_15") (pintype "bidirectional"))
    )
    (net (code "61") (name "unconnected-(U2-GP2-Pad14)") (class "Default")
      (node (ref "U2") (pin "14") (pinfunction "GP2_14") (pintype "bidirectional"))
    )
    (net (code "62") (name "unconnected-(U2-GP6-Pad6)") (class "Default")
      (node (ref "U2") (pin "6") (pinfunction "GP6_6") (pintype "bidirectional"))
    )
    (net (code "63") (name "unconnected-(U2-GP7-Pad5)") (class "Default")
      (node (ref "U2") (pin "5") (pinfunction "GP7_5") (pintype "bidirectional"))
    )
    (net (code "64") (name "unconnected-(U2-RTS-Pad11)") (class "Default")
      (node (ref "U2") (pin "11") (pinfunction "RTS_11") (pintype "bidirectional"))
    )
    (net (code "65") (name "unconnected-(U3-CD-PadP$10)") (class "Default")
      (node (ref "U3") (pin "P$10") (pinfunction "CD_P$10") (pintype "bidirectional"))
    )
    (net (code "66") (name "unconnected-(U3-GND2-PadP$9)") (class "Default")
      (node (ref "U3") (pin "P$9") (pinfunction "GND2_P$9") (pintype "bidirectional"))
    )
    (net (code "67") (name "unconnected-(U4-PA01(XOUT32{slash}SER1:1{slash}TC2:1)-Pad2)") (class "Default")
      (node (ref "U4") (pin "2") (pinfunction "PA01(XOUT32/SER1:1/TC2:1)_2") (pintype "bidirectional"))
    )
    (net (code "68") (name "unconnected-(U4-PA02(AIN0{slash}DAC)-Pad3)") (class "Default")
      (node (ref "U4") (pin "3") (pinfunction "PA02(AIN0/DAC)_3") (pintype "bidirectional"))
    )
    (net (code "69") (name "unconnected-(U4-PA03(AIN1{slash}REFA)-Pad4)") (class "Default")
      (node (ref "U4") (pin "4") (pinfunction "PA03(AIN1/REFA)_4") (pintype "bidirectional"))
    )
    (net (code "70") (name "unconnected-(U4-PA04(AIN4{slash}REFB{slash}SER0:0{slash}TC0:0)-Pad9)") (class "Default")
      (node (ref "U4") (pin "9") (pinfunction "PA04(AIN4/REFB/SER0:0/TC0:0)_9") (pintype "bidirectional"))
    )
    (net (code "71") (name "unconnected-(U4-PA05(AIN5{slash}SER0:1{slash}TC0:1)-Pad10)") (class "Default")
      (node (ref "U4") (pin "10") (pinfunction "PA05(AIN5/SER0:1/TC0:1)_10") (pintype "bidirectional"))
    )
    (net (code "72") (name "unconnected-(U4-PA06(AIN6{slash}SER0:2{slash}TC1:0)-Pad11)") (class "Default")
      (node (ref "U4") (pin "11") (pinfunction "PA06(AIN6/SER0:2/TC1:0)_11") (pintype "bidirectional"))
    )
    (net (code "73") (name "unconnected-(U4-PA07(AIN7{slash}SER0:3{slash}TC1:1)-Pad12)") (class "Default")
      (node (ref "U4") (pin "12") (pinfunction "PA07(AIN7/SER0:3/TC1:1)_12") (pintype "bidirectional"))
    )
    (net (code "74") (name "unconnected-(U4-PA08(I2C{slash}AIN16{slash}SER0:0+)-Pad13)") (class "Default")
      (node (ref "U4") (pin "13") (pinfunction "PA08(I2C/AIN16/SER0:0+)_13") (pintype "bidirectional"))
    )
    (net (code "75") (name "unconnected-(U4-PA09(I2C{slash}AIN17{slash}SER0:1+)-Pad14)") (class "Default")
      (node (ref "U4") (pin "14") (pinfunction "PA09(I2C/AIN17/SER0:1+)_14") (pintype "bidirectional"))
    )
    (net (code "76") (name "unconnected-(U4-PA10(AIN18{slash}SER0:2+)-Pad15)") (class "Default")
      (node (ref "U4") (pin "15") (pinfunction "PA10(AIN18/SER0:2+)_15") (pintype "bidirectional"))
    )
    (net (code "77") (name "unconnected-(U4-PA11(AIN19{slash}SER0:3+)-Pad16)") (class "Default")
      (node (ref "U4") (pin "16") (pinfunction "PA11(AIN19/SER0:3+)_16") (pintype "bidirectional"))
    )
    (net (code "78") (name "unconnected-(U4-PA12(I2C{slash}SER2:0+)-Pad21)") (class "Default")
      (node (ref "U4") (pin "21") (pinfunction "PA12(I2C/SER2:0+)_21") (pintype "bidirectional"))
    )
    (net (code "79") (name "unconnected-(U4-PA13(I2C{slash}SER2:1+)-Pad22)") (class "Default")
      (node (ref "U4") (pin "22") (pinfunction "PA13(I2C/SER2:1+)_22") (pintype "bidirectional"))
    )
    (net (code "80") (name "unconnected-(U4-PA14(XIN{slash}SER2:2+)-Pad23)") (class "Default")
      (node (ref "U4") (pin "23") (pinfunction "PA14(XIN/SER2:2+)_23") (pintype "bidirectional"))
    )
    (net (code "81") (name "unconnected-(U4-PA15(XOUT{slash}SER2:3+)-Pad24)") (class "Default")
      (node (ref "U4") (pin "24") (pinfunction "PA15(XOUT/SER2:3+)_24") (pintype "bidirectional"))
    )
    (net (code "82") (name "unconnected-(U4-PA16(I2C{slash}SER1:0+)-Pad25)") (class "Default")
      (node (ref "U4") (pin "25") (pinfunction "PA16(I2C/SER1:0+)_25") (pintype "bidirectional"))
    )
    (net (code "83") (name "unconnected-(U4-PA17(I2C{slash}SER1:1+)-Pad26)") (class "Default")
      (node (ref "U4") (pin "26") (pinfunction "PA17(I2C/SER1:1+)_26") (pintype "bidirectional"))
    )
    (net (code "84") (name "unconnected-(U4-PA18(SER1:2+)-Pad27)") (class "Default")
      (node (ref "U4") (pin "27") (pinfunction "PA18(SER1:2+)_27") (pintype "bidirectional"))
    )
    (net (code "85") (name "unconnected-(U4-PA19(SER1:3+)-Pad28)") (class "Default")
      (node (ref "U4") (pin "28") (pinfunction "PA19(SER1:3+)_28") (pintype "bidirectional"))
    )
    (net (code "86") (name "unconnected-(U4-PA20(SER5:2+)-Pad29)") (class "Default")
      (node (ref "U4") (pin "29") (pinfunction "PA20(SER5:2+)_29") (pintype "bidirectional"))
    )
    (net (code "87") (name "unconnected-(U4-PA21(SER5:3+)-Pad30)") (class "Default")
      (node (ref "U4") (pin "30") (pinfunction "PA21(SER5:3+)_30") (pintype "bidirectional"))
    )
    (net (code "88") (name "unconnected-(U4-PA22(I2C{slash}SER3:0+)-Pad31)") (class "Default")
      (node (ref "U4") (pin "31") (pinfunction "PA22(I2C/SER3:0+)_31") (pintype "bidirectional"))
    )
    (net (code "89") (name "unconnected-(U4-PA23(I2C{slash}SER3:0+)-Pad32)") (class "Default")
      (node (ref "U4") (pin "32") (pinfunction "PA23(I2C/SER3:0+)_32") (pintype "bidirectional"))
    )
    (net (code "90") (name "unconnected-(U4-PA27-Pad39)") (class "Default")
      (node (ref "U4") (pin "39") (pinfunction "PA27_39") (pintype "bidirectional"))
    )
    (net (code "91") (name "unconnected-(U4-PA28-Pad41)") (class "Default")
      (node (ref "U4") (pin "41") (pinfunction "PA28_41") (pintype "bidirectional"))
    )
    (net (code "92") (name "unconnected-(U4-PB08(AIN2{slash}SER4:0{slash}TC4:0)-Pad7)") (class "Default")
      (node (ref "U4") (pin "7") (pinfunction "PB08(AIN2/SER4:0/TC4:0)_7") (pintype "bidirectional"))
    )
    (net (code "93") (name "unconnected-(U4-PB09(AIN3{slash}SER4:1{slash}TC4:1)-Pad8)") (class "Default")
      (node (ref "U4") (pin "8") (pinfunction "PB09(AIN3/SER4:1/TC4:1)_8") (pintype "bidirectional"))
    )
    (net (code "94") (name "unconnected-(U4-PB10(SER4:2+)-Pad19)") (class "Default")
      (node (ref "U4") (pin "19") (pinfunction "PB10(SER4:2+)_19") (pintype "bidirectional"))
    )
    (net (code "95") (name "unconnected-(U4-PB11(SER4:3+)-Pad20)") (class "Default")
      (node (ref "U4") (pin "20") (pinfunction "PB11(SER4:3+)_20") (pintype "bidirectional"))
    )
    (net (code "96") (name "unconnected-(U4-PB22(SER5:2+)-Pad37)") (class "Default")
      (node (ref "U4") (pin "37") (pinfunction "PB22(SER5:2+)_37") (pintype "bidirectional"))
    )
    (net (code "97") (name "unconnected-(U4-PB23(SER5:3+)-Pad38)") (class "Default")
      (node (ref "U4") (pin "38") (pinfunction "PB23(SER5:3+)_38") (pintype "bidirectional"))
    )
    (net (code "98") (name "unconnected-(USB1-PadID)") (class "Default")
      (node (ref "USB1") (pin "ID") (pinfunction "ID_ID") (pintype "bidirectional"))
    )
    (net (code "99") (name "unconnected-(USB2-PadID)") (class "Default")
      (node (ref "USB2") (pin "ID") (pinfunction "ID_ID") (pintype "bidirectional"))
    )
  )
)
